# bbf-thonkjacks.net
KiCad netlist of a schematic drawn in EAGLE
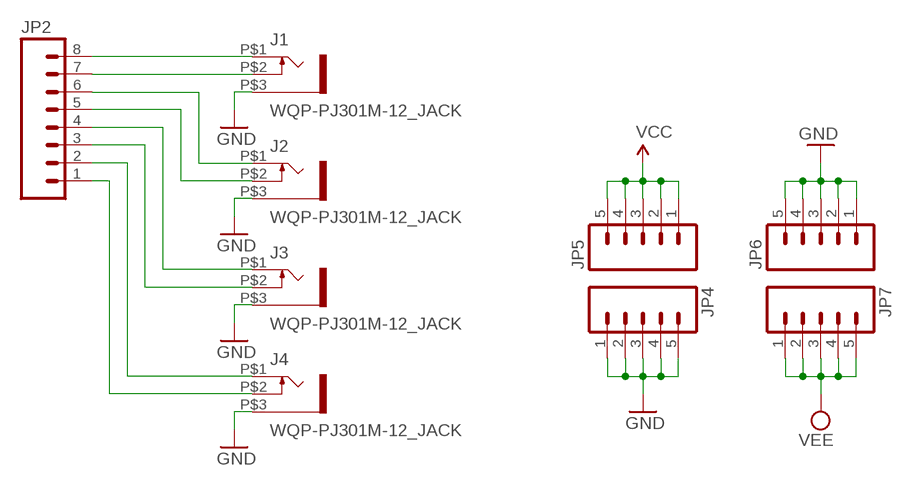
[diagram p0: schematic, sheet 1]

(export (version "E")
  (design (tool "Eeschema 10.0.6"))
  (components
    (comp (ref "J1")
      (value "WQP-PJ301M-12_JACK")
      (footprint "eagle-import:WQP-PJ301M-12_JACK")
      (libsource (lib "eagle-import") (part "WQP-PJ301M-12_JACK"))
    )
    (comp (ref "J2")
      (value "WQP-PJ301M-12_JACK")
      (footprint "eagle-import:WQP-PJ301M-12_JACK")
      (libsource (lib "eagle-import") (part "WQP-PJ301M-12_JACK"))
    )
    (comp (ref "J3")
      (value "WQP-PJ301M-12_JACK")
      (footprint "eagle-import:WQP-PJ301M-12_JACK")
      (libsource (lib "eagle-import") (part "WQP-PJ301M-12_JACK"))
    )
    (comp (ref "J4")
      (value "WQP-PJ301M-12_JACK")
      (footprint "eagle-import:WQP-PJ301M-12_JACK")
      (libsource (lib "eagle-import") (part "WQP-PJ301M-12_JACK"))
    )
    (comp (ref "JP2")
      (value "M08")
      (footprint "eagle-import:1X08")
      (libsource (lib "eagle-import") (part "M08"))
    )
    (comp (ref "JP4")
      (value "M05PTH")
      (footprint "eagle-import:1X05")
      (libsource (lib "eagle-import") (part "M05PTH"))
    )
    (comp (ref "JP5")
      (value "M05PTH")
      (footprint "eagle-import:1X05")
      (libsource (lib "eagle-import") (part "M05PTH"))
    )
    (comp (ref "JP6")
      (value "M05PTH")
      (footprint "eagle-import:1X05")
      (libsource (lib "eagle-import") (part "M05PTH"))
    )
    (comp (ref "JP7")
      (value "M05PTH")
      (footprint "eagle-import:1X05")
      (libsource (lib "eagle-import") (part "M05PTH"))
    )
  )
  (nets
    (net (code "1") (name "GND") (class "Default")
      (node (ref "J1") (pin "P$3") (pinfunction "1_P$3") (pintype "passive"))
      (node (ref "J2") (pin "P$3") (pinfunction "1_P$3") (pintype "passive"))
      (node (ref "J3") (pin "P$3") (pinfunction "1_P$3") (pintype "passive"))
      (node (ref "J4") (pin "P$3") (pinfunction "1_P$3") (pintype "passive"))
      (node (ref "JP4") (pin "1") (pinfunction "1_1") (pintype "passive"))
      (node (ref "JP4") (pin "2") (pinfunction "2_2") (pintype "passive"))
      (node (ref "JP4") (pin "3") (pinfunction "3_3") (pintype "passive"))
      (node (ref "JP4") (pin "4") (pinfunction "4_4") (pintype "passive"))
      (node (ref "JP4") (pin "5") (pinfunction "5_5") (pintype "passive"))
      (node (ref "JP6") (pin "1") (pinfunction "1_1") (pintype "passive"))
      (node (ref "JP6") (pin "2") (pinfunction "2_2") (pintype "passive"))
      (node (ref "JP6") (pin "3") (pinfunction "3_3") (pintype "passive"))
      (node (ref "JP6") (pin "4") (pinfunction "4_4") (pintype "passive"))
      (node (ref "JP6") (pin "5") (pinfunction "5_5") (pintype "passive"))
    )
    (net (code "2") (name "Net-(J1-2)") (class "Default")
      (node (ref "J1") (pin "P$1") (pinfunction "2_P$1") (pintype "passive"))
      (node (ref "JP2") (pin "8") (pinfunction "8_8") (pintype "passive"))
    )
    (net (code "3") (name "Net-(J1-3)") (class "Default")
      (node (ref "J1") (pin "P$2") (pinfunction "3_P$2") (pintype "passive"))
      (node (ref "JP2") (pin "7") (pinfunction "7_7") (pintype "passive"))
    )
    (net (code "4") (name "Net-(J2-2)") (class "Default")
      (node (ref "J2") (pin "P$1") (pinfunction "2_P$1") (pintype "passive"))
      (node (ref "JP2") (pin "6") (pinfunction "6_6") (pintype "passive"))
    )
    (net (code "5") (name "Net-(J2-3)") (class "Default")
      (node (ref "J2") (pin "P$2") (pinfunction "3_P$2") (pintype "passive"))
      (node (ref "JP2") (pin "5") (pinfunction "5_5") (pintype "passive"))
    )
    (net (code "6") (name "Net-(J3-2)") (class "Default")
      (node (ref "J3") (pin "P$1") (pinfunction "2_P$1") (pintype "passive"))
      (node (ref "JP2") (pin "4") (pinfunction "4_4") (pintype "passive"))
    )
    (net (code "7") (name "Net-(J3-3)") (class "Default")
      (node (ref "J3") (pin "P$2") (pinfunction "3_P$2") (pintype "passive"))
      (node (ref "JP2") (pin "3") (pinfunction "3_3") (pintype "passive"))
    )
    (net (code "8") (name "Net-(J4-2)") (class "Default")
      (node (ref "J4") (pin "P$1") (pinfunction "2_P$1") (pintype "passive"))
      (node (ref "JP2") (pin "2") (pinfunction "2_2") (pintype "passive"))
    )
    (net (code "9") (name "Net-(J4-3)") (class "Default")
      (node (ref "J4") (pin "P$2") (pinfunction "3_P$2") (pintype "passive"))
      (node (ref "JP2") (pin "1") (pinfunction "1_1") (pintype "passive"))
    )
    (net (code "10") (name "VCC") (class "Default")
      (node (ref "JP5") (pin "1") (pinfunction "1_1") (pintype "passive"))
      (node (ref "JP5") (pin "2") (pinfunction "2_2") (pintype "passive"))
      (node (ref "JP5") (pin "3") (pinfunction "3_3") (pintype "passive"))
      (node (ref "JP5") (pin "4") (pinfunction "4_4") (pintype "passive"))
      (node (ref "JP5") (pin "5") (pinfunction "5_5") (pintype "passive"))
    )
    (net (code "11") (name "VEE") (class "Default")
      (node (ref "JP7") (pin "1") (pinfunction "1_1") (pintype "passive"))
      (node (ref "JP7") (pin "2") (pinfunction "2_2") (pintype "passive"))
      (node (ref "JP7") (pin "3") (pinfunction "3_3") (pintype "passive"))
      (node (ref "JP7") (pin "4") (pinfunction "4_4") (pintype "passive"))
      (node (ref "JP7") (pin "5") (pinfunction "5_5") (pintype "passive"))
    )
  )
)
